# SL_Power.net
KiCad netlist of a schematic drawn in Altium Designer
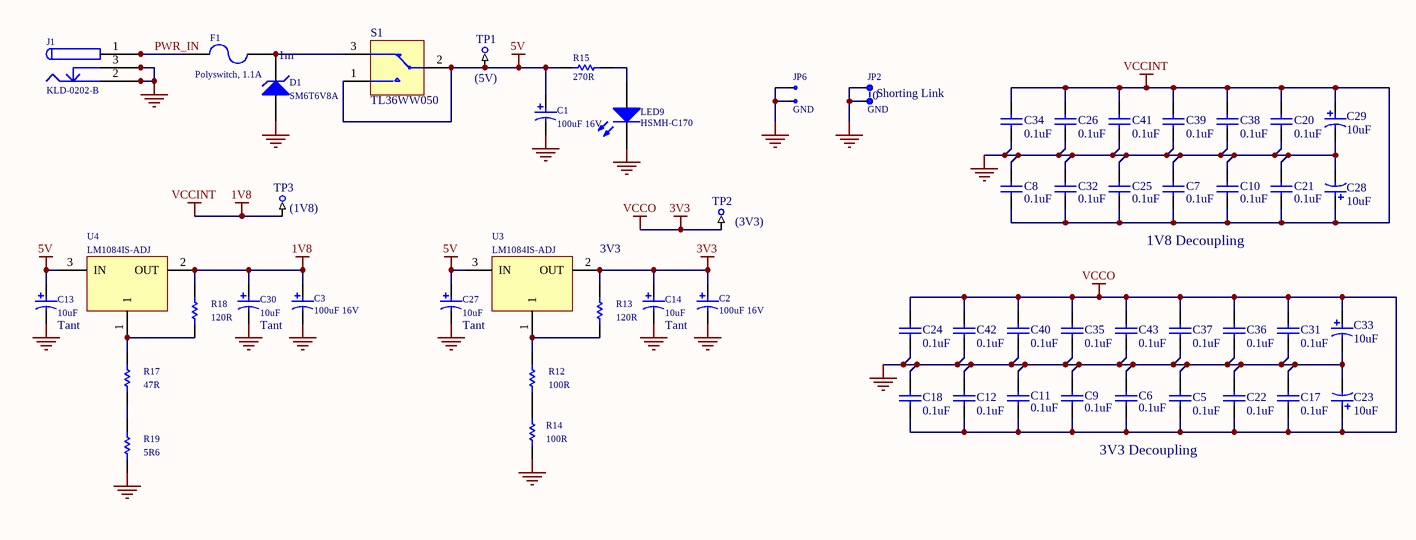
[diagram p0: SL_Power.SchDoc]

(export (version "E")
  (design (tool "Eeschema 10.0.6"))
  (components
    (comp (ref "C1")
      (value "100uF 16V")
      (footprint "CAPPR2-5x6.8")
      (description "Polar Capacitor")
      (libsource (lib "Altium Nanoboard Project") (part "CAP_POLAR"))
    )
    (comp (ref "C2")
      (value "100uF 16V")
      (footprint "CAPPR2-5x6.8")
      (description "Polar Capacitor")
      (libsource (lib "Altium Nanoboard Project") (part "CAP_POLAR"))
    )
    (comp (ref "C3")
      (value "100uF 16V")
      (footprint "CAPPR2-5x6.8")
      (description "Polar Capacitor")
      (libsource (lib "Altium Nanoboard Project") (part "CAP_POLAR"))
    )
    (comp (ref "C5")
      (value "0.1uF")
      (footprint "Altium Nanoboard Project:CC2012-0805")
      (description "Capacitor")
      (libsource (lib "Altium Nanoboard Project") (part "CAP"))
    )
    (comp (ref "C6")
      (value "0.1uF")
      (footprint "Altium Nanoboard Project:CC2012-0805")
      (description "Capacitor")
      (libsource (lib "Altium Nanoboard Project") (part "CAP"))
    )
    (comp (ref "C7")
      (value "0.1uF")
      (footprint "Altium Nanoboard Project:CC2012-0805")
      (description "Capacitor")
      (libsource (lib "Altium Nanoboard Project") (part "CAP"))
    )
    (comp (ref "C8")
      (value "0.1uF")
      (footprint "Altium Nanoboard Project:CC2012-0805")
      (description "Capacitor")
      (libsource (lib "Altium Nanoboard Project") (part "CAP"))
    )
    (comp (ref "C9")
      (value "0.1uF")
      (footprint "Altium Nanoboard Project:CC2012-0805")
      (description "Capacitor")
      (libsource (lib "Altium Nanoboard Project") (part "CAP"))
    )
    (comp (ref "C10")
      (value "0.1uF")
      (footprint "Altium Nanoboard Project:CC2012-0805")
      (description "Capacitor")
      (libsource (lib "Altium Nanoboard Project") (part "CAP"))
    )
    (comp (ref "C11")
      (value "0.1uF")
      (footprint "Altium Nanoboard Project:CC2012-0805")
      (description "Capacitor")
      (libsource (lib "Altium Nanoboard Project") (part "CAP"))
    )
    (comp (ref "C12")
      (value "0.1uF")
      (footprint "Altium Nanoboard Project:CC2012-0805")
      (description "Capacitor")
      (libsource (lib "Altium Nanoboard Project") (part "CAP"))
    )
    (comp (ref "C13")
      (value "10uF")
      (footprint "Altium Nanoboard Project:MCCT-B")
      (description "Polar Capacitor")
      (fields (field (name "CAPACITOR TYPE") "Tant"))
      (libsource (lib "Altium Nanoboard Project") (part "CAP_POLAR"))
    )
    (comp (ref "C14")
      (value "10uF")
      (footprint "Altium Nanoboard Project:MCCT-B")
      (description "Polar Capacitor")
      (fields (field (name "CAPACITOR TYPE") "Tant"))
      (libsource (lib "Altium Nanoboard Project") (part "CAP_POLAR"))
    )
    (comp (ref "C17")
      (value "0.1uF")
      (footprint "Altium Nanoboard Project:CC2012-0805")
      (description "Capacitor")
      (libsource (lib "Altium Nanoboard Project") (part "CAP"))
    )
    (comp (ref "C18")
      (value "0.1uF")
      (footprint "Altium Nanoboard Project:CC2012-0805")
      (description "Capacitor")
      (libsource (lib "Altium Nanoboard Project") (part "CAP"))
    )
    (comp (ref "C20")
      (value "0.1uF")
      (footprint "Altium Nanoboard Project:CC2012-0805")
      (description "Capacitor")
      (libsource (lib "Altium Nanoboard Project") (part "CAP"))
    )
    (comp (ref "C21")
      (value "0.1uF")
      (footprint "Altium Nanoboard Project:CC2012-0805")
      (description "Capacitor")
      (libsource (lib "Altium Nanoboard Project") (part "CAP"))
    )
    (comp (ref "C22")
      (value "0.1uF")
      (footprint "Altium Nanoboard Project:CC2012-0805")
      (description "Capacitor")
      (libsource (lib "Altium Nanoboard Project") (part "CAP"))
    )
    (comp (ref "C23")
      (value "10uF")
      (footprint "Altium Nanoboard Project:MCCT-B")
      (description "Polar Capacitor")
      (libsource (lib "Altium Nanoboard Project") (part "CAP_POLAR"))
    )
    (comp (ref "C24")
      (value "0.1uF")
      (footprint "Altium Nanoboard Project:CC2012-0805")
      (description "Capacitor")
      (libsource (lib "Altium Nanoboard Project") (part "CAP"))
    )
    (comp (ref "C25")
      (value "0.1uF")
      (footprint "Altium Nanoboard Project:CC2012-0805")
      (description "Capacitor")
      (libsource (lib "Altium Nanoboard Project") (part "CAP"))
    )
    (comp (ref "C26")
      (value "0.1uF")
      (footprint "Altium Nanoboard Project:CC2012-0805")
      (description "Capacitor")
      (libsource (lib "Altium Nanoboard Project") (part "CAP"))
    )
    (comp (ref "C27")
      (value "10uF")
      (footprint "Altium Nanoboard Project:MCCT-B")
      (description "Polar Capacitor")
      (fields (field (name "CAPACITOR TYPE") "Tant"))
      (libsource (lib "Altium Nanoboard Project") (part "CAP_POLAR"))
    )
    (comp (ref "C28")
      (value "10uF")
      (footprint "Altium Nanoboard Project:MCCT-B")
      (description "Polar Capacitor")
      (libsource (lib "Altium Nanoboard Project") (part "CAP_POLAR"))
    )
    (comp (ref "C29")
      (value "10uF")
      (footprint "Altium Nanoboard Project:MCCT-B")
      (description "Polar Capacitor")
      (libsource (lib "Altium Nanoboard Project") (part "CAP_POLAR"))
    )
    (comp (ref "C30")
      (value "10uF")
      (footprint "Altium Nanoboard Project:MCCT-B")
      (description "Polar Capacitor")
      (fields (field (name "CAPACITOR TYPE") "Tant"))
      (libsource (lib "Altium Nanoboard Project") (part "CAP_POLAR"))
    )
    (comp (ref "C31")
      (value "0.1uF")
      (footprint "Altium Nanoboard Project:CC2012-0805")
      (description "Capacitor")
      (libsource (lib "Altium Nanoboard Project") (part "CAP"))
    )
    (comp (ref "C32")
      (value "0.1uF")
      (footprint "Altium Nanoboard Project:CC2012-0805")
      (description "Capacitor")
      (libsource (lib "Altium Nanoboard Project") (part "CAP"))
    )
    (comp (ref "C33")
      (value "10uF")
      (footprint "Altium Nanoboard Project:MCCT-B")
      (description "Polar Capacitor")
      (libsource (lib "Altium Nanoboard Project") (part "CAP_POLAR"))
    )
    (comp (ref "C34")
      (value "0.1uF")
      (footprint "Altium Nanoboard Project:CC2012-0805")
      (description "Capacitor")
      (libsource (lib "Altium Nanoboard Project") (part "CAP"))
    )
    (comp (ref "C35")
      (value "0.1uF")
      (footprint "Altium Nanoboard Project:CC2012-0805")
      (description "Capacitor")
      (libsource (lib "Altium Nanoboard Project") (part "CAP"))
    )
    (comp (ref "C36")
      (value "0.1uF")
      (footprint "Altium Nanoboard Project:CC2012-0805")
      (description "Capacitor")
      (libsource (lib "Altium Nanoboard Project") (part "CAP"))
    )
    (comp (ref "C37")
      (value "0.1uF")
      (footprint "Altium Nanoboard Project:CC2012-0805")
      (description "Capacitor")
      (libsource (lib "Altium Nanoboard Project") (part "CAP"))
    )
    (comp (ref "C38")
      (value "0.1uF")
      (footprint "Altium Nanoboard Project:CC2012-0805")
      (description "Capacitor")
      (libsource (lib "Altium Nanoboard Project") (part "CAP"))
    )
    (comp (ref "C39")
      (value "0.1uF")
      (footprint "Altium Nanoboard Project:CC2012-0805")
      (description "Capacitor")
      (libsource (lib "Altium Nanoboard Project") (part "CAP"))
    )
    (comp (ref "C40")
      (value "0.1uF")
      (footprint "Altium Nanoboard Project:CC2012-0805")
      (description "Capacitor")
      (libsource (lib "Altium Nanoboard Project") (part "CAP"))
    )
    (comp (ref "C41")
      (value "0.1uF")
      (footprint "Altium Nanoboard Project:CC2012-0805")
      (description "Capacitor")
      (libsource (lib "Altium Nanoboard Project") (part "CAP"))
    )
    (comp (ref "C42")
      (value "0.1uF")
      (footprint "Altium Nanoboard Project:CC2012-0805")
      (description "Capacitor")
      (libsource (lib "Altium Nanoboard Project") (part "CAP"))
    )
    (comp (ref "C43")
      (value "0.1uF")
      (footprint "Altium Nanoboard Project:CC2012-0805")
      (description "Capacitor")
      (libsource (lib "Altium Nanoboard Project") (part "CAP"))
    )
    (comp (ref "D1")
      (value "SM6T6V8A")
      (footprint "Altium Nanoboard Project:DO214")
      (description "Zener Diode, 6.2V, 5W")
      (fields (field (name "MANUFACTURER") "Microsemi"))
      (libsource (lib "Altium Nanoboard Project") (part "BZG03C13"))
    )
    (comp (ref "F1")
      (value "Polyswitch, 1.1A")
      (footprint "RUE160_0.2")
      (description "Polyswitch 1.1A, Raychem RUE110")
      (fields (field (name "ALTIUM_VALUE") "1m"))
      (libsource (lib "Miscellaneous Devices") (part "Fuse 2"))
    )
    (comp (ref "J1")
      (value "KLD-0202-B")
      (footprint "Altium Nanoboard Project:KLD-0202")
      (description "Low Voltage Power Supply Connector")
      (fields (field (name "MANUFACTURER") "Kycon"))
      (libsource (lib "Altium Nanoboard Project") (part "KLD-0202-B"))
    )
    (comp (ref "JP2")
      (value "GND")
      (footprint "Altium Nanoboard Project:HDR1X2")
      (description "Jumper, 2-Pin")
      (libsource (lib "SpiritLevel_2E") (part "Jumper, 2-Pin"))
    )
    (comp (ref "JP6")
      (value "GND")
      (footprint "Altium Nanoboard Project:HDR1X2")
      (description "Jumper, 2-Pin")
      (libsource (lib "SpiritLevel_2E") (part "Jumper, 2-Pin"))
    )
    (comp (ref "JS1")
      (value "Shorting Link")
      (description "Shorting Link, 2.54mm (0.1\") Pitch")
      (fields (field (name "ALTIUM_VALUE") "0"))
      (libsource (lib "SpiritLevel_2E") (part "Jumper Socket"))
    )
    (comp (ref "LED9")
      (value "HSMH-C170")
      (footprint "Altium Nanoboard Project:SMD _LED")
      (description "Typical RED GaAs SMD LED Agilent make")
      (libsource (lib "Altium Nanoboard Project") (part "HSMX-C670"))
    )
    (comp (ref "R12")
      (value "100R")
      (footprint "Altium Nanoboard Project:CC2012-0805")
      (description "Resistor")
      (libsource (lib "Altium Nanoboard Project") (part "RES"))
    )
    (comp (ref "R13")
      (value "120R")
      (footprint "Altium Nanoboard Project:CC2012-0805")
      (description "Resistor")
      (libsource (lib "Altium Nanoboard Project") (part "RES"))
    )
    (comp (ref "R14")
      (value "100R")
      (footprint "Altium Nanoboard Project:CC2012-0805")
      (description "Resistor")
      (libsource (lib "Altium Nanoboard Project") (part "RES"))
    )
    (comp (ref "R15")
      (value "270R")
      (footprint "CR2012-0805")
      (description "Resistor")
      (libsource (lib "PassiveSMD") (part "RES"))
    )
    (comp (ref "R17")
      (value "47R")
      (footprint "Altium Nanoboard Project:CC2012-0805")
      (description "Resistor")
      (libsource (lib "Altium Nanoboard Project") (part "RES"))
    )
    (comp (ref "R18")
      (value "120R")
      (footprint "Altium Nanoboard Project:CC2012-0805")
      (description "Resistor")
      (libsource (lib "Altium Nanoboard Project") (part "RES"))
    )
    (comp (ref "R19")
      (value "5R6")
      (footprint "Altium Nanoboard Project:CC2012-0805")
      (description "Resistor")
      (libsource (lib "Altium Nanoboard Project") (part "RES"))
    )
    (comp (ref "S1")
      (value "TL36WW050")
      (footprint "PCB_SWITCH")
      (description "SPDT Subminiature Toggle Switch")
      (libsource (lib "Switches and display") (part "PCB_MOUNT_SWITCH"))
    )
    (comp (ref "TP1") (value "(5V)") (footprint "TP") (libsource (lib "ChrisSchematic") (part "TestPin")))
    (comp (ref "TP2") (value "(3V3)") (footprint "TP") (libsource (lib "ChrisSchematic") (part "TestPin")))
    (comp (ref "TP3") (value "(1V8)") (footprint "TP") (libsource (lib "ChrisSchematic") (part "TestPin")))
    (comp (ref "U3")
      (value "LM1084IS-ADJ")
      (footprint "Altium Nanoboard Project:TO-263")
      (description "5A Low Dropout Possitive Regulators")
      (libsource (lib "Altium Nanoboard Project") (part "LM1084IS-ADJ"))
    )
    (comp (ref "U4")
      (value "LM1084IS-ADJ")
      (footprint "Altium Nanoboard Project:TO-263")
      (description "5A Low Dropout Possitive Regulators")
      (libsource (lib "Altium Nanoboard Project") (part "LM1084IS-ADJ"))
    )
  )
  (nets
    (net (code "1") (name "/PWR_IN") (class "Default")
      (node (ref "F1") (pin "1") (pinfunction "1_1") (pintype "passive"))
      (node (ref "J1") (pin "1") (pintype "power_in"))
      (node (ref "J1") (pin "1A") (pintype "power_in"))
      (node (ref "J1") (pin "1B") (pintype "power_in"))
    )
    (net (code "2") (name "1V8") (class "Default")
      (node (ref "C10") (pin "1") (pinfunction "1_1") (pintype "passive"))
      (node (ref "C20") (pin "1") (pinfunction "1_1") (pintype "passive"))
      (node (ref "C21") (pin "1") (pinfunction "1_1") (pintype "passive"))
      (node (ref "C25") (pin "1") (pinfunction "1_1") (pintype "passive"))
      (node (ref "C26") (pin "1") (pinfunction "1_1") (pintype "passive"))
      (node (ref "C28") (pin "1") (pinfunction "1_1") (pintype "passive"))
      (node (ref "C29") (pin "1") (pinfunction "1_1") (pintype "passive"))
      (node (ref "C3") (pin "1") (pinfunction "1_1") (pintype "passive"))
      (node (ref "C30") (pin "1") (pinfunction "1_1") (pintype "passive"))
      (node (ref "C32") (pin "1") (pinfunction "1_1") (pintype "passive"))
      (node (ref "C34") (pin "2") (pinfunction "2_2") (pintype "passive"))
      (node (ref "C38") (pin "1") (pinfunction "1_1") (pintype "passive"))
      (node (ref "C39") (pin "1") (pinfunction "1_1") (pintype "passive"))
      (node (ref "C41") (pin "1") (pinfunction "1_1") (pintype "passive"))
      (node (ref "C7") (pin "1") (pinfunction "1_1") (pintype "passive"))
      (node (ref "C8") (pin "1") (pinfunction "1_1") (pintype "passive"))
      (node (ref "R18") (pin "1") (pinfunction "1_1") (pintype "passive"))
      (node (ref "TP3") (pin "1") (pinfunction "1_1") (pintype "input"))
      (node (ref "U4") (pin "2") (pinfunction "OUT_2") (pintype "power_in"))
    )
    (net (code "3") (name "3V3") (class "Default")
      (node (ref "C11") (pin "1") (pinfunction "1_1") (pintype "passive"))
      (node (ref "C12") (pin "1") (pinfunction "1_1") (pintype "passive"))
      (node (ref "C14") (pin "1") (pinfunction "1_1") (pintype "passive"))
      (node (ref "C17") (pin "2") (pinfunction "2_2") (pintype "passive"))
      (node (ref "C18") (pin "2") (pinfunction "2_2") (pintype "passive"))
      (node (ref "C2") (pin "1") (pinfunction "1_1") (pintype "passive"))
      (node (ref "C22") (pin "2") (pinfunction "2_2") (pintype "passive"))
      (node (ref "C23") (pin "1") (pinfunction "1_1") (pintype "passive"))
      (node (ref "C24") (pin "2") (pinfunction "2_2") (pintype "passive"))
      (node (ref "C31") (pin "1") (pinfunction "1_1") (pintype "passive"))
      (node (ref "C33") (pin "1") (pinfunction "1_1") (pintype "passive"))
      (node (ref "C35") (pin "1") (pinfunction "1_1") (pintype "passive"))
      (node (ref "C36") (pin "2") (pinfunction "2_2") (pintype "passive"))
      (node (ref "C37") (pin "1") (pinfunction "1_1") (pintype "passive"))
      (node (ref "C40") (pin "1") (pinfunction "1_1") (pintype "passive"))
      (node (ref "C42") (pin "1") (pinfunction "1_1") (pintype "passive"))
      (node (ref "C43") (pin "1") (pinfunction "1_1") (pintype "passive"))
      (node (ref "C5") (pin "2") (pinfunction "2_2") (pintype "passive"))
      (node (ref "C6") (pin "1") (pinfunction "1_1") (pintype "passive"))
      (node (ref "C9") (pin "1") (pinfunction "1_1") (pintype "passive"))
      (node (ref "R13") (pin "1") (pinfunction "1_1") (pintype "passive"))
      (node (ref "TP2") (pin "1") (pinfunction "1_1") (pintype "input"))
      (node (ref "U3") (pin "2") (pinfunction "OUT_2") (pintype "power_in"))
    )
    (net (code "4") (name "5V") (class "Default")
      (node (ref "C1") (pin "1") (pinfunction "1_1") (pintype "passive"))
      (node (ref "C13") (pin "1") (pinfunction "1_1") (pintype "passive"))
      (node (ref "C27") (pin "1") (pinfunction "1_1") (pintype "passive"))
      (node (ref "R15") (pin "2") (pinfunction "2_2") (pintype "passive"))
      (node (ref "S1") (pin "1") (pintype "passive"))
      (node (ref "S1") (pin "2") (pintype "passive"))
      (node (ref "TP1") (pin "1") (pinfunction "1_1") (pintype "input"))
      (node (ref "U3") (pin "3") (pinfunction "IN_3") (pintype "power_in"))
      (node (ref "U4") (pin "3") (pinfunction "IN_3") (pintype "power_in"))
    )
    (net (code "5") (name "GND") (class "Default")
      (node (ref "C1") (pin "2") (pinfunction "2_2") (pintype "passive"))
      (node (ref "C10") (pin "2") (pinfunction "2_2") (pintype "passive"))
      (node (ref "C11") (pin "2") (pinfunction "2_2") (pintype "passive"))
      (node (ref "C12") (pin "2") (pinfunction "2_2") (pintype "passive"))
      (node (ref "C13") (pin "2") (pinfunction "2_2") (pintype "passive"))
      (node (ref "C14") (pin "2") (pinfunction "2_2") (pintype "passive"))
      (node (ref "C17") (pin "1") (pinfunction "1_1") (pintype "passive"))
      (node (ref "C18") (pin "1") (pinfunction "1_1") (pintype "passive"))
      (node (ref "C2") (pin "2") (pinfunction "2_2") (pintype "passive"))
      (node (ref "C20") (pin "2") (pinfunction "2_2") (pintype "passive"))
      (node (ref "C21") (pin "2") (pinfunction "2_2") (pintype "passive"))
      (node (ref "C22") (pin "1") (pinfunction "1_1") (pintype "passive"))
      (node (ref "C23") (pin "2") (pinfunction "2_2") (pintype "passive"))
      (node (ref "C24") (pin "1") (pinfunction "1_1") (pintype "passive"))
      (node (ref "C25") (pin "2") (pinfunction "2_2") (pintype "passive"))
      (node (ref "C26") (pin "2") (pinfunction "2_2") (pintype "passive"))
      (node (ref "C27") (pin "2") (pinfunction "2_2") (pintype "passive"))
      (node (ref "C28") (pin "2") (pinfunction "2_2") (pintype "passive"))
      (node (ref "C29") (pin "2") (pinfunction "2_2") (pintype "passive"))
      (node (ref "C3") (pin "2") (pinfunction "2_2") (pintype "passive"))
      (node (ref "C30") (pin "2") (pinfunction "2_2") (pintype "passive"))
      (node (ref "C31") (pin "2") (pinfunction "2_2") (pintype "passive"))
      (node (ref "C32") (pin "2") (pinfunction "2_2") (pintype "passive"))
      (node (ref "C33") (pin "2") (pinfunction "2_2") (pintype "passive"))
      (node (ref "C34") (pin "1") (pinfunction "1_1") (pintype "passive"))
      (node (ref "C35") (pin "2") (pinfunction "2_2") (pintype "passive"))
      (node (ref "C36") (pin "1") (pinfunction "1_1") (pintype "passive"))
      (node (ref "C37") (pin "2") (pinfunction "2_2") (pintype "passive"))
      (node (ref "C38") (pin "2") (pinfunction "2_2") (pintype "passive"))
      (node (ref "C39") (pin "2") (pinfunction "2_2") (pintype "passive"))
      (node (ref "C40") (pin "2") (pinfunction "2_2") (pintype "passive"))
      (node (ref "C41") (pin "2") (pinfunction "2_2") (pintype "passive"))
      (node (ref "C42") (pin "2") (pinfunction "2_2") (pintype "passive"))
      (node (ref "C43") (pin "2") (pinfunction "2_2") (pintype "passive"))
      (node (ref "C5") (pin "1") (pinfunction "1_1") (pintype "passive"))
      (node (ref "C6") (pin "2") (pinfunction "2_2") (pintype "passive"))
      (node (ref "C7") (pin "2") (pinfunction "2_2") (pintype "passive"))
      (node (ref "C8") (pin "2") (pinfunction "2_2") (pintype "passive"))
      (node (ref "C9") (pin "2") (pinfunction "2_2") (pintype "passive"))
      (node (ref "D1") (pin "1") (pinfunction "A_1") (pintype "passive"))
      (node (ref "J1") (pin "2") (pintype "power_in"))
      (node (ref "J1") (pin "2A") (pintype "power_in"))
      (node (ref "J1") (pin "2B") (pintype "power_in"))
      (node (ref "J1") (pin "3") (pintype "power_in"))
      (node (ref "J1") (pin "3A") (pintype "power_in"))
      (node (ref "J1") (pin "3B") (pintype "power_in"))
      (node (ref "JP2") (pin "1") (pinfunction "1_1") (pintype "passive"))
      (node (ref "JP2") (pin "2") (pinfunction "2_2") (pintype "passive"))
      (node (ref "JP6") (pin "1") (pinfunction "1_1") (pintype "passive"))
      (node (ref "JP6") (pin "2") (pinfunction "2_2") (pintype "passive"))
      (node (ref "LED9") (pin "2") (pinfunction "K_2") (pintype "passive"))
      (node (ref "R14") (pin "1") (pinfunction "1_1") (pintype "passive"))
      (node (ref "R19") (pin "2") (pinfunction "2_2") (pintype "passive"))
    )
    (net (code "6") (name "Net-(D1-K)") (class "Default")
      (node (ref "D1") (pin "2") (pinfunction "K_2") (pintype "passive"))
      (node (ref "F1") (pin "2") (pinfunction "2_2") (pintype "passive"))
      (node (ref "S1") (pin "3") (pintype "passive"))
    )
    (net (code "7") (name "Net-(LED9-A)") (class "Default")
      (node (ref "LED9") (pin "1") (pinfunction "A_1") (pintype "passive"))
      (node (ref "R15") (pin "1") (pinfunction "1_1") (pintype "passive"))
    )
    (net (code "8") (name "Net-(R12-Pad1)") (class "Default")
      (node (ref "R12") (pin "1") (pinfunction "1_1") (pintype "passive"))
      (node (ref "R13") (pin "2") (pinfunction "2_2") (pintype "passive"))
      (node (ref "U3") (pin "1") (pinfunction "1_1") (pintype "passive"))
    )
    (net (code "9") (name "Net-(R12-Pad2)") (class "Default")
      (node (ref "R12") (pin "2") (pinfunction "2_2") (pintype "passive"))
      (node (ref "R14") (pin "2") (pinfunction "2_2") (pintype "passive"))
    )
    (net (code "10") (name "Net-(R17-Pad1)") (class "Default")
      (node (ref "R17") (pin "1") (pinfunction "1_1") (pintype "passive"))
      (node (ref "R18") (pin "2") (pinfunction "2_2") (pintype "passive"))
      (node (ref "U4") (pin "1") (pinfunction "1_1") (pintype "passive"))
    )
    (net (code "11") (name "Net-(R17-Pad2)") (class "Default")
      (node (ref "R17") (pin "2") (pinfunction "2_2") (pintype "passive"))
      (node (ref "R19") (pin "1") (pinfunction "1_1") (pintype "passive"))
    )
  )
)
